# Adafruit_TCA4307.net
KiCad netlist of a schematic drawn in EAGLE
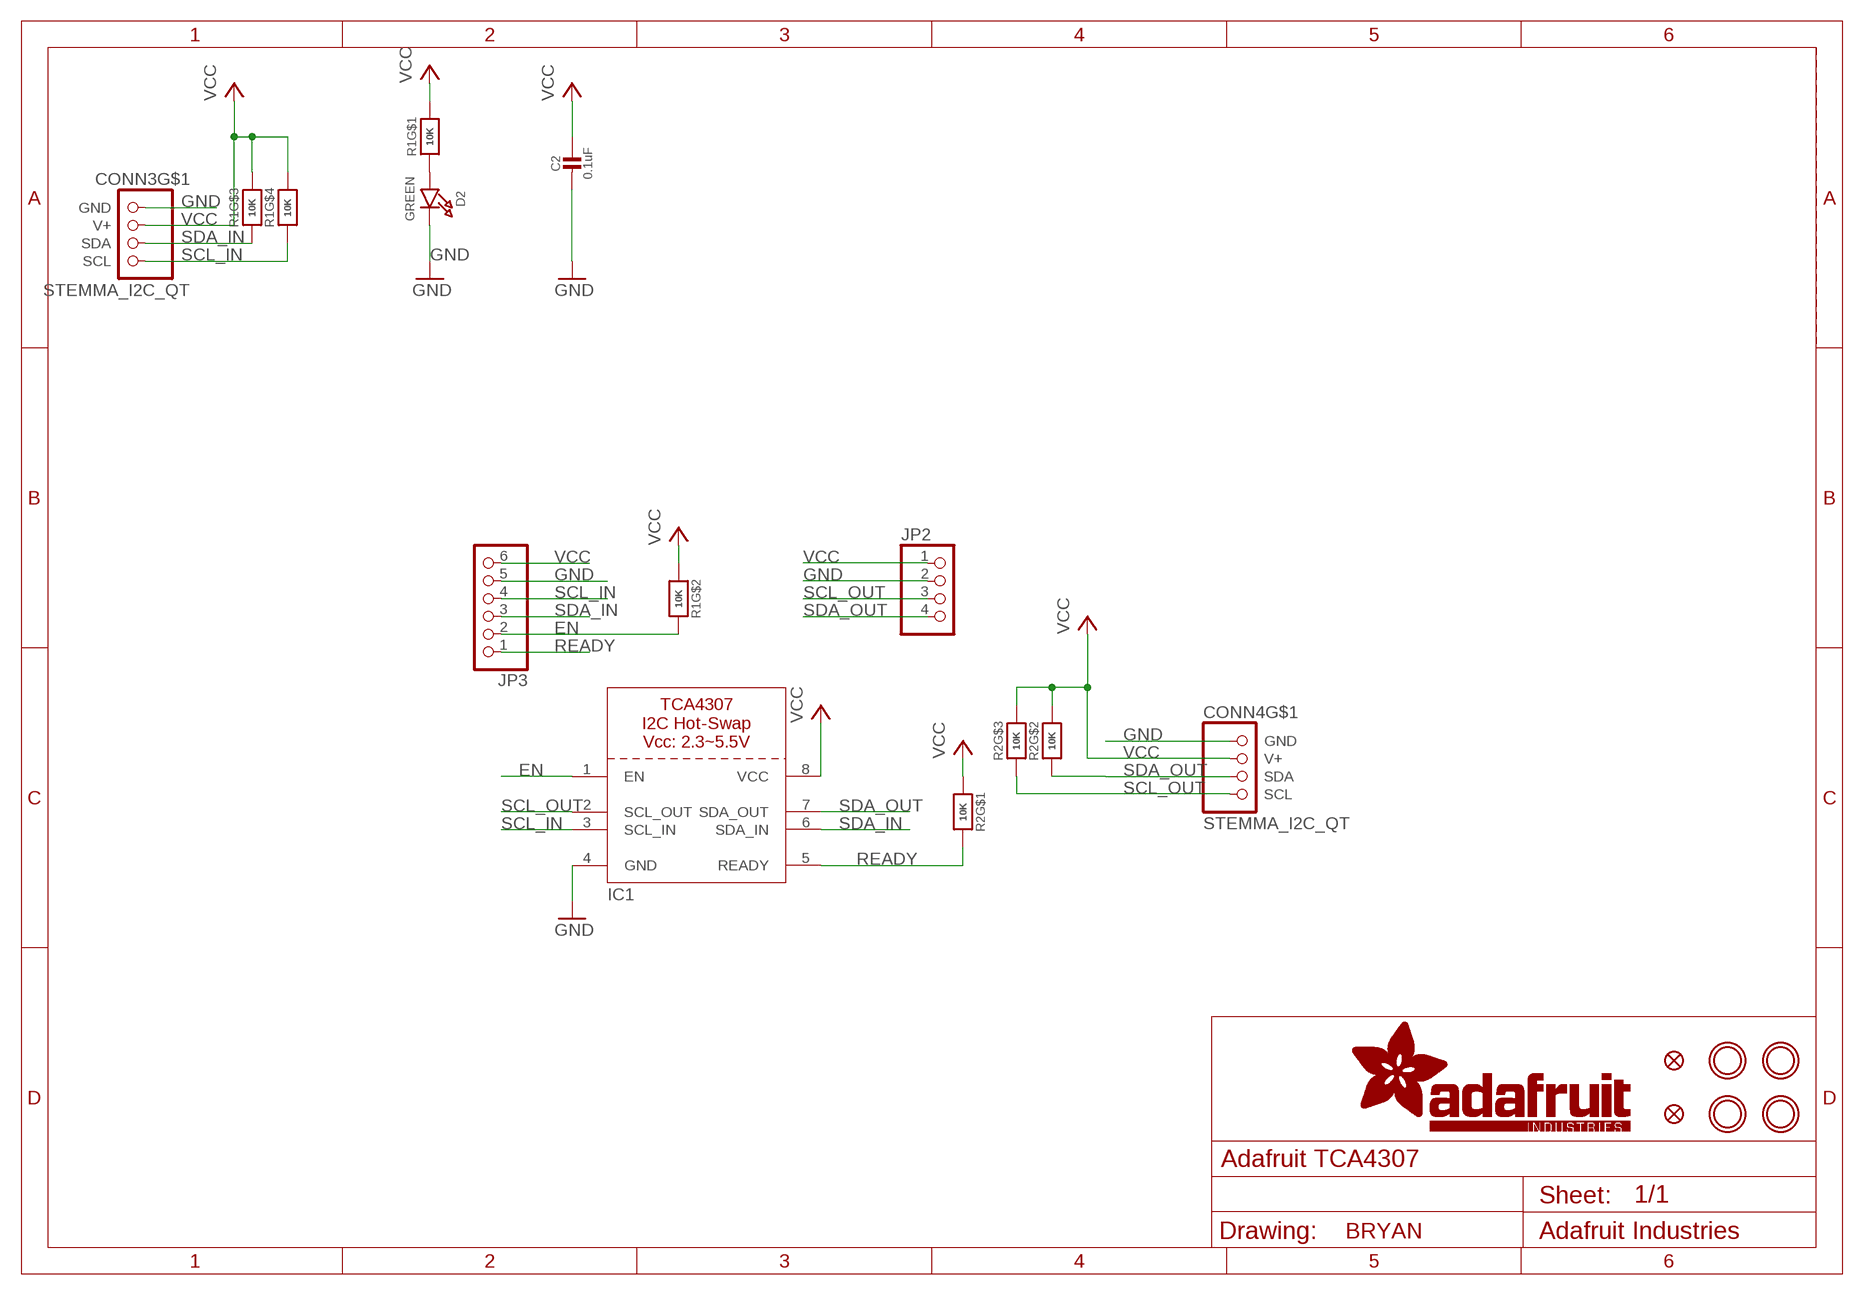
[diagram p0: schematic, sheet 1]

(export (version "E")
  (design (tool "Eeschema 10.0.6"))
  (components
    (comp (ref "C2")
      (value "0.1uF")
      (footprint "eagle-import:0603-NO")
      (libsource (lib "eagle-import") (part "CAP_CERAMIC0603_NO"))
    )
    (comp (ref "CONN3")
      (value "STEMMA_I2C_QT")
      (footprint "eagle-import:JST_SH4")
      (libsource (lib "eagle-import") (part "STEMMA_I2C_QT"))
    )
    (comp (ref "CONN4")
      (value "STEMMA_I2C_QT")
      (footprint "eagle-import:JST_SH4")
      (libsource (lib "eagle-import") (part "STEMMA_I2C_QT"))
    )
    (comp (ref "D2")
      (value "GREEN")
      (footprint "eagle-import:CHIPLED_0603_NOOUTLINE")
      (libsource (lib "eagle-import") (part "LED0603_NOOUTLINE"))
    )
    (comp (ref "FID3")
      (value "FIDUCIAL_1MM")
      (footprint "eagle-import:FIDUCIAL_1MM")
      (libsource (lib "eagle-import") (part "FIDUCIAL_1MM"))
    )
    (comp (ref "FID4")
      (value "FIDUCIAL_1MM")
      (footprint "eagle-import:FIDUCIAL_1MM")
      (libsource (lib "eagle-import") (part "FIDUCIAL_1MM"))
    )
    (comp (ref "IC1")
      (value "TCA4307")
      (footprint "eagle-import:TSSOP8")
      (libsource (lib "eagle-import") (part "TCA4307"))
    )
    (comp (ref "JP2")
      (value "HEADER-1X4ROUND")
      (footprint "eagle-import:1X04_ROUND")
      (libsource (lib "eagle-import") (part "HEADER-1X4ROUND"))
    )
    (comp (ref "JP3")
      (value "HEADER-1X670MIL")
      (footprint "eagle-import:1X06_ROUND_70")
      (libsource (lib "eagle-import") (part "HEADER-1X670MIL"))
    )
    (comp (ref "R1")
      (value "10K")
      (footprint "eagle-import:RESPACK_4X0603")
      (libsource (lib "eagle-import") (part "RESISTOR_4PACK"))
    )
    (comp (ref "R2")
      (value "10K")
      (footprint "eagle-import:RESPACK_4X0603")
      (libsource (lib "eagle-import") (part "RESISTOR_4PACK"))
    )
    (comp (ref "U$1")
      (value "MOUNTINGHOLE2.5")
      (footprint "eagle-import:MOUNTINGHOLE_2.5_PLATED")
      (libsource (lib "eagle-import") (part "MOUNTINGHOLE2.5"))
    )
    (comp (ref "U$17")
      (value "MOUNTINGHOLE2.5")
      (footprint "eagle-import:MOUNTINGHOLE_2.5_PLATED")
      (libsource (lib "eagle-import") (part "MOUNTINGHOLE2.5"))
    )
    (comp (ref "U$19")
      (value "MOUNTINGHOLE2.5")
      (footprint "eagle-import:MOUNTINGHOLE_2.5_PLATED")
      (libsource (lib "eagle-import") (part "MOUNTINGHOLE2.5"))
    )
    (comp (ref "U$21")
      (value "MOUNTINGHOLE2.5")
      (footprint "eagle-import:MOUNTINGHOLE_2.5_PLATED")
      (libsource (lib "eagle-import") (part "MOUNTINGHOLE2.5"))
    )
  )
  (nets
    (net (code "1") (name "/EN") (class "Default")
      (node (ref "IC1") (pin "1") (pinfunction "EN_1") (pintype "bidirectional"))
      (node (ref "JP3") (pin "2") (pinfunction "2_2") (pintype "passive"))
      (node (ref "R1") (pin "7") (pinfunction "2_7") (pintype "passive"))
    )
    (net (code "2") (name "/READY") (class "Default")
      (node (ref "IC1") (pin "5") (pinfunction "READY_5") (pintype "bidirectional"))
      (node (ref "JP3") (pin "1") (pinfunction "1_1") (pintype "passive"))
      (node (ref "R2") (pin "8") (pinfunction "2_8") (pintype "passive"))
    )
    (net (code "3") (name "/SCL_IN") (class "Default")
      (node (ref "CONN3") (pin "4") (pinfunction "SCL_4") (pintype "passive"))
      (node (ref "IC1") (pin "3") (pinfunction "SCL_IN_3") (pintype "bidirectional"))
      (node (ref "JP3") (pin "4") (pinfunction "4_4") (pintype "passive"))
      (node (ref "R1") (pin "4") (pinfunction "1_4") (pintype "passive"))
    )
    (net (code "4") (name "/SCL_OUT") (class "Default")
      (node (ref "CONN4") (pin "4") (pinfunction "SCL_4") (pintype "passive"))
      (node (ref "IC1") (pin "2") (pinfunction "SCL_OUT_2") (pintype "bidirectional"))
      (node (ref "JP2") (pin "3") (pinfunction "3_3") (pintype "passive"))
      (node (ref "R2") (pin "3") (pinfunction "1_3") (pintype "passive"))
    )
    (net (code "5") (name "/SDA_IN") (class "Default")
      (node (ref "CONN3") (pin "3") (pinfunction "SDA_3") (pintype "passive"))
      (node (ref "IC1") (pin "6") (pinfunction "SDA_IN_6") (pintype "bidirectional"))
      (node (ref "JP3") (pin "3") (pinfunction "3_3") (pintype "passive"))
      (node (ref "R1") (pin "3") (pinfunction "1_3") (pintype "passive"))
    )
    (net (code "6") (name "/SDA_OUT") (class "Default")
      (node (ref "CONN4") (pin "3") (pinfunction "SDA_3") (pintype "passive"))
      (node (ref "IC1") (pin "7") (pinfunction "SDA_OUT_7") (pintype "bidirectional"))
      (node (ref "JP2") (pin "4") (pinfunction "4_4") (pintype "passive"))
      (node (ref "R2") (pin "2") (pinfunction "1_2") (pintype "passive"))
    )
    (net (code "7") (name "GND") (class "Default")
      (node (ref "C2") (pin "2") (pinfunction "2_2") (pintype "passive"))
      (node (ref "CONN3") (pin "1") (pinfunction "GND_1") (pintype "passive"))
      (node (ref "CONN4") (pin "1") (pinfunction "GND_1") (pintype "passive"))
      (node (ref "D2") (pin "C") (pinfunction "C_C") (pintype "passive"))
      (node (ref "IC1") (pin "4") (pinfunction "GND_4") (pintype "bidirectional"))
      (node (ref "JP2") (pin "2") (pinfunction "2_2") (pintype "passive"))
      (node (ref "JP3") (pin "5") (pinfunction "5_5") (pintype "passive"))
    )
    (net (code "8") (name "Net-(D2-PadA)") (class "Default")
      (node (ref "D2") (pin "A") (pinfunction "A_A") (pintype "passive"))
      (node (ref "R1") (pin "1") (pinfunction "1_1") (pintype "passive"))
    )
    (net (code "9") (name "VCC") (class "Default")
      (node (ref "C2") (pin "1") (pinfunction "1_1") (pintype "passive"))
      (node (ref "CONN3") (pin "2") (pinfunction "V+_2") (pintype "passive"))
      (node (ref "CONN4") (pin "2") (pinfunction "V+_2") (pintype "passive"))
      (node (ref "IC1") (pin "8") (pinfunction "VCC_8") (pintype "bidirectional"))
      (node (ref "JP2") (pin "1") (pinfunction "1_1") (pintype "passive"))
      (node (ref "JP3") (pin "6") (pinfunction "6_6") (pintype "passive"))
      (node (ref "R1") (pin "2") (pinfunction "1_2") (pintype "passive"))
      (node (ref "R1") (pin "5") (pinfunction "2_5") (pintype "passive"))
      (node (ref "R1") (pin "6") (pinfunction "2_6") (pintype "passive"))
      (node (ref "R1") (pin "8") (pinfunction "2_8") (pintype "passive"))
      (node (ref "R2") (pin "1") (pinfunction "1_1") (pintype "passive"))
      (node (ref "R2") (pin "6") (pinfunction "2_6") (pintype "passive"))
      (node (ref "R2") (pin "7") (pinfunction "2_7") (pintype "passive"))
    )
  )
)
